# PCB-AC2SLb.net
KiCad netlist of a schematic drawn in EAGLE
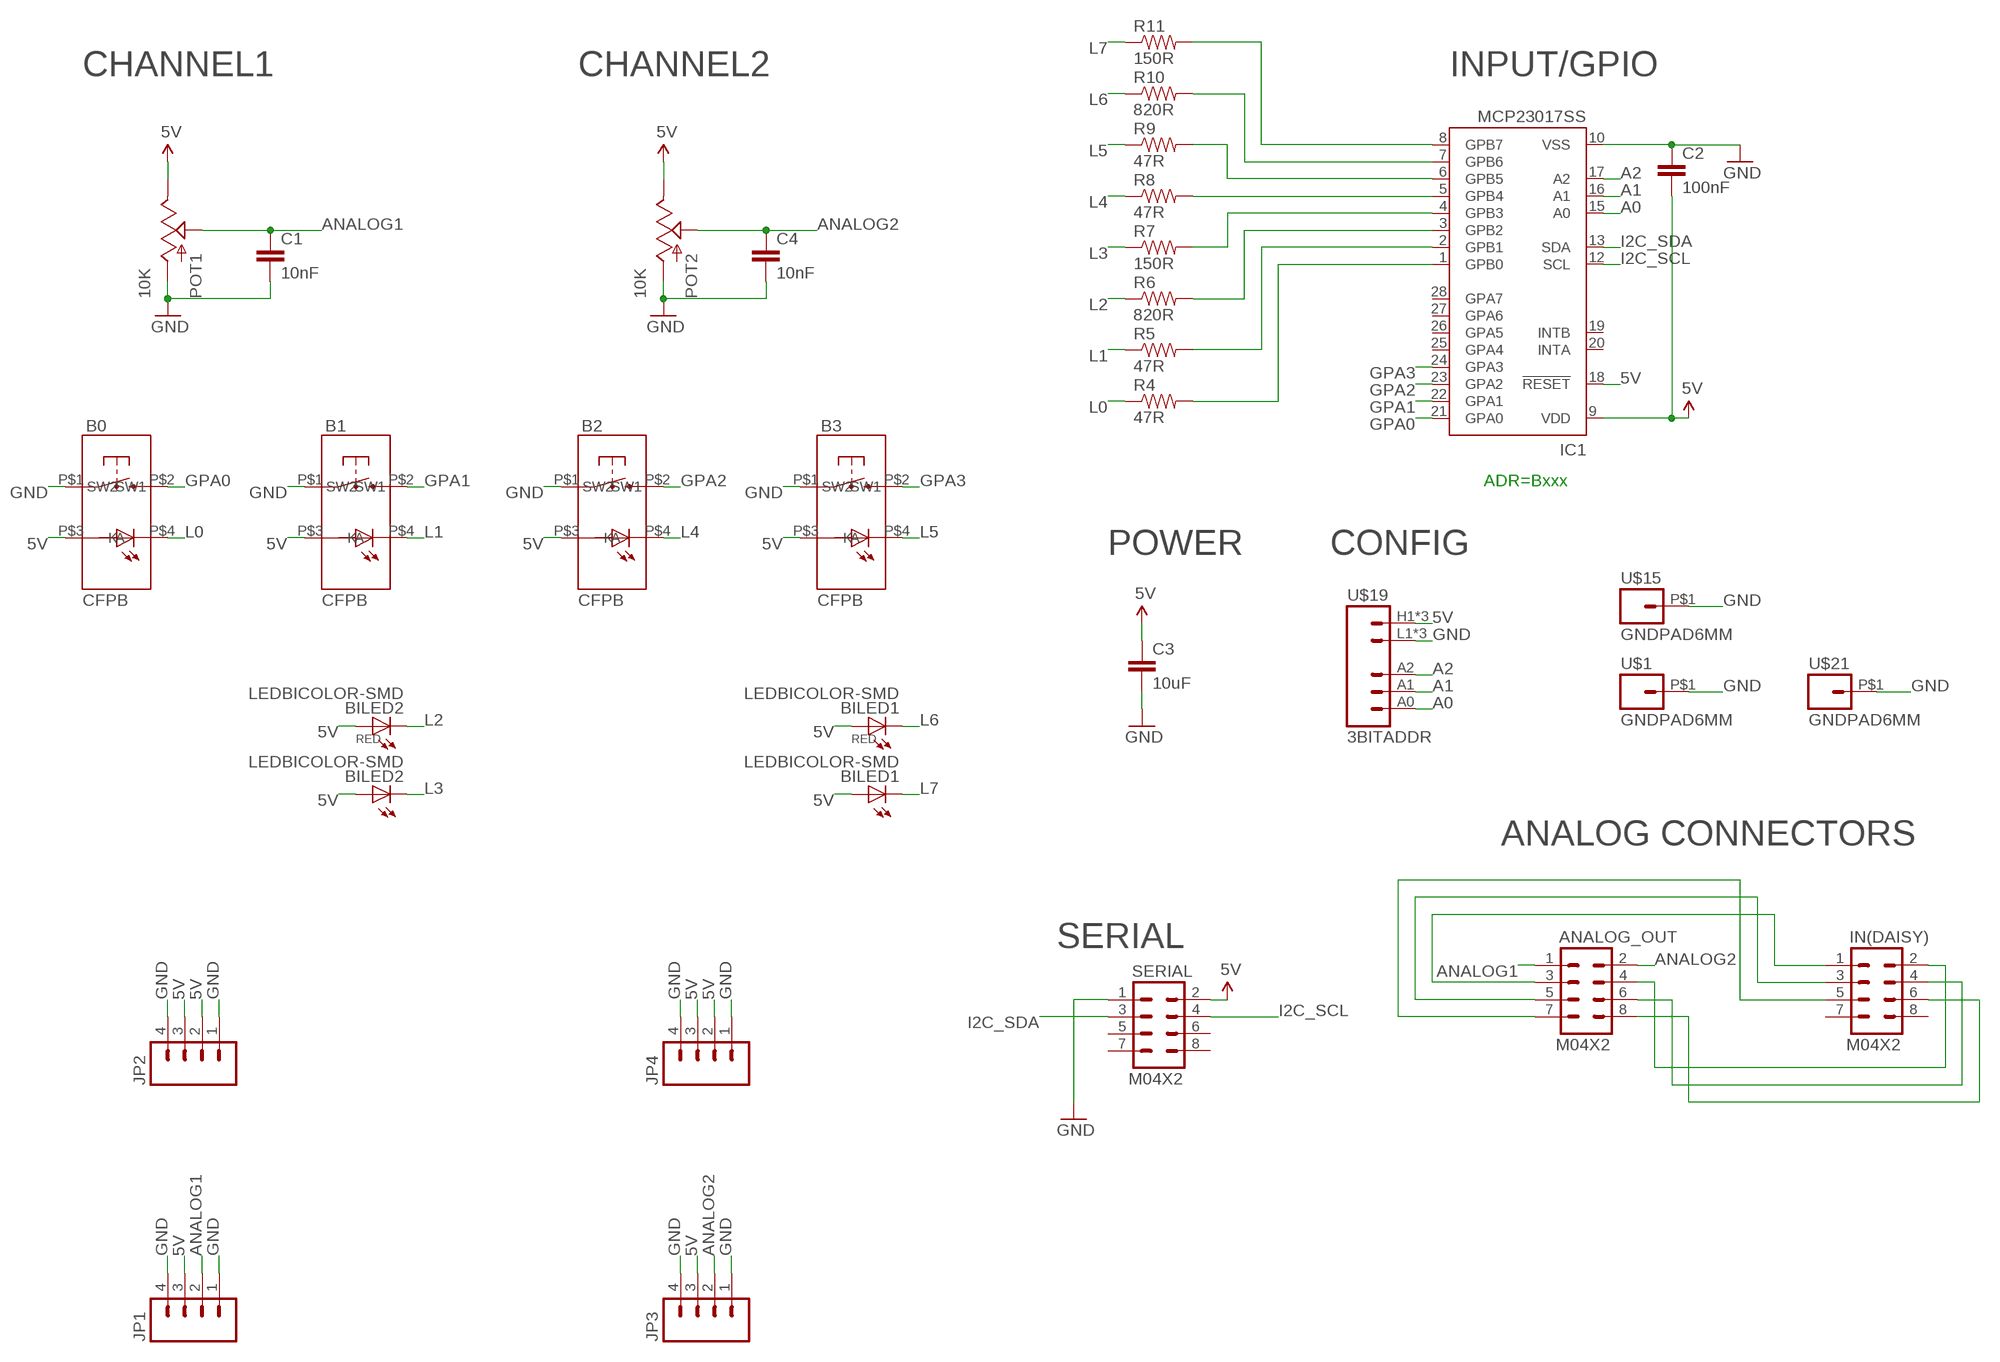
[diagram p0: schematic, sheet 1]

(export (version "E")
  (design (tool "Eeschema 10.0.6"))
  (components
    (comp (ref "ANALOG_OUT")
      (value "M04X2")
      (footprint "eagle-import:2X4")
      (libsource (lib "eagle-import") (part "M04X2"))
    )
    (comp (ref "B0")
      (value "CFPB")
      (footprint "eagle-import:CFPB-6_9MM")
      (libsource (lib "eagle-import") (part "CFPB"))
    )
    (comp (ref "B1")
      (value "CFPB")
      (footprint "eagle-import:CFPB-6_9MM")
      (libsource (lib "eagle-import") (part "CFPB"))
    )
    (comp (ref "B2")
      (value "CFPB")
      (footprint "eagle-import:CFPB-6_9MM")
      (libsource (lib "eagle-import") (part "CFPB"))
    )
    (comp (ref "B3")
      (value "CFPB")
      (footprint "eagle-import:CFPB-6_9MM")
      (libsource (lib "eagle-import") (part "CFPB"))
    )
    (comp (ref "BILED1")
      (value "LEDBICOLOR-SMD")
      (footprint "eagle-import:LEDBICOLOR-SMD")
      (libsource (lib "eagle-import") (part "LEDBICOLOR-SMD"))
    )
    (comp (ref "BILED2")
      (value "LEDBICOLOR-SMD")
      (footprint "eagle-import:LEDBICOLOR-SMD")
      (libsource (lib "eagle-import") (part "LEDBICOLOR-SMD"))
    )
    (comp (ref "C1")
      (value "10nF")
      (footprint "eagle-import:0603-CAP")
      (libsource (lib "eagle-import") (part "CAP0603-CAP"))
    )
    (comp (ref "C2")
      (value "100nF")
      (footprint "eagle-import:0603-CAP")
      (libsource (lib "eagle-import") (part "CAP0603-CAP"))
    )
    (comp (ref "C3")
      (value "10uF")
      (footprint "eagle-import:0805")
      (libsource (lib "eagle-import") (part "CAP0805"))
    )
    (comp (ref "C4")
      (value "10nF")
      (footprint "eagle-import:0603-CAP")
      (libsource (lib "eagle-import") (part "CAP0603-CAP"))
    )
    (comp (ref "IC1")
      (value "MCP23017SS")
      (footprint "eagle-import:SSOP28")
      (fields
        (field (name "MF") "MICROCHIP")
        (field (name "MPN") "MCP23017-E/SS")
        (field (name "MPN_1") "MCP23017-E/SS")
        (field (name "OC_FARNELL") "1467674")
        (field (name "OC_NEWARK") "31K2960")
      )
      (libsource (lib "eagle-import") (part "MCP23017SS"))
    )
    (comp (ref "IN(DAISY)")
      (value "M04X2")
      (footprint "eagle-import:2X4")
      (libsource (lib "eagle-import") (part "M04X2"))
    )
    (comp (ref "JP1")
      (value "M04PTH")
      (footprint "eagle-import:1X04")
      (libsource (lib "eagle-import") (part "M04PTH"))
    )
    (comp (ref "JP2")
      (value "M04PTH")
      (footprint "eagle-import:1X04")
      (libsource (lib "eagle-import") (part "M04PTH"))
    )
    (comp (ref "JP3")
      (value "M04PTH")
      (footprint "eagle-import:1X04")
      (libsource (lib "eagle-import") (part "M04PTH"))
    )
    (comp (ref "JP4")
      (value "M04PTH")
      (footprint "eagle-import:1X04")
      (libsource (lib "eagle-import") (part "M04PTH"))
    )
    (comp (ref "POT1")
      (value "10K")
      (footprint "eagle-import:SLIDER45")
      (libsource (lib "eagle-import") (part "SLIDER45"))
    )
    (comp (ref "POT2")
      (value "10K")
      (footprint "eagle-import:SLIDER45")
      (libsource (lib "eagle-import") (part "SLIDER45"))
    )
    (comp (ref "R4")
      (value "47R")
      (footprint "eagle-import:0603-RES")
      (libsource (lib "eagle-import") (part "RESISTOR0603-RES"))
    )
    (comp (ref "R5")
      (value "47R")
      (footprint "eagle-import:0603-RES")
      (libsource (lib "eagle-import") (part "RESISTOR0603-RES"))
    )
    (comp (ref "R6")
      (value "820R")
      (footprint "eagle-import:0603-RES")
      (libsource (lib "eagle-import") (part "RESISTOR0603-RES"))
    )
    (comp (ref "R7")
      (value "150R")
      (footprint "eagle-import:0603-RES")
      (libsource (lib "eagle-import") (part "RESISTOR0603-RES"))
    )
    (comp (ref "R8")
      (value "47R")
      (footprint "eagle-import:0603-RES")
      (libsource (lib "eagle-import") (part "RESISTOR0603-RES"))
    )
    (comp (ref "R9")
      (value "47R")
      (footprint "eagle-import:0603-RES")
      (libsource (lib "eagle-import") (part "RESISTOR0603-RES"))
    )
    (comp (ref "R10")
      (value "820R")
      (footprint "eagle-import:0603-RES")
      (libsource (lib "eagle-import") (part "RESISTOR0603-RES"))
    )
    (comp (ref "R11")
      (value "150R")
      (footprint "eagle-import:0603-RES")
      (libsource (lib "eagle-import") (part "RESISTOR0603-RES"))
    )
    (comp (ref "SERIAL")
      (value "M04X2")
      (footprint "eagle-import:2X4")
      (libsource (lib "eagle-import") (part "M04X2"))
    )
    (comp (ref "U$1")
      (value "GNDPAD6MM")
      (footprint "eagle-import:3.2MMPAD6MM")
      (libsource (lib "eagle-import") (part "GNDPAD6MM"))
    )
    (comp (ref "U$15")
      (value "GNDPAD6MM")
      (footprint "eagle-import:3.2MMPAD6MM")
      (libsource (lib "eagle-import") (part "GNDPAD6MM"))
    )
    (comp (ref "U$19")
      (value "3BITADDR")
      (footprint "eagle-import:3BITADDR")
      (libsource (lib "eagle-import") (part "3BITADDR"))
    )
    (comp (ref "U$21")
      (value "GNDPAD6MM")
      (footprint "eagle-import:3.2MMPAD6MM")
      (libsource (lib "eagle-import") (part "GNDPAD6MM"))
    )
  )
  (nets
    (net (code "1") (name "5V") (class "Default")
      (node (ref "B0") (pin "P$3") (pinfunction "A_P$3") (pintype "bidirectional"))
      (node (ref "B1") (pin "P$3") (pinfunction "A_P$3") (pintype "bidirectional"))
      (node (ref "B2") (pin "P$3") (pinfunction "A_P$3") (pintype "bidirectional"))
      (node (ref "B3") (pin "P$3") (pinfunction "A_P$3") (pintype "bidirectional"))
      (node (ref "BILED1") (pin "P$1") (pinfunction "A_P$1") (pintype "passive"))
      (node (ref "BILED1") (pin "P$3") (pinfunction "A1_P$3") (pintype "passive"))
      (node (ref "BILED2") (pin "P$1") (pinfunction "A_P$1") (pintype "passive"))
      (node (ref "BILED2") (pin "P$3") (pinfunction "A1_P$3") (pintype "passive"))
      (node (ref "C2") (pin "2") (pinfunction "2_2") (pintype "passive"))
      (node (ref "C3") (pin "1") (pinfunction "1_1") (pintype "passive"))
      (node (ref "IC1") (pin "18") (pinfunction "~{RESET}_18") (pintype "input"))
      (node (ref "IC1") (pin "9") (pinfunction "VDD_9") (pintype "power_in"))
      (node (ref "JP1") (pin "3") (pinfunction "3_3") (pintype "passive"))
      (node (ref "JP2") (pin "2") (pinfunction "2_2") (pintype "passive"))
      (node (ref "JP2") (pin "3") (pinfunction "3_3") (pintype "passive"))
      (node (ref "JP3") (pin "3") (pinfunction "3_3") (pintype "passive"))
      (node (ref "JP4") (pin "2") (pinfunction "2_2") (pintype "passive"))
      (node (ref "JP4") (pin "3") (pinfunction "3_3") (pintype "passive"))
      (node (ref "POT1") (pin "1") (pinfunction "E_1") (pintype "passive"))
      (node (ref "POT2") (pin "1") (pinfunction "E_1") (pintype "passive"))
      (node (ref "SERIAL") (pin "2") (pinfunction "2_2") (pintype "passive"))
      (node (ref "U$19") (pin "H1") (pinfunction "VCC_H1") (pintype "passive"))
      (node (ref "U$19") (pin "H2") (pinfunction "VCC_H2") (pintype "passive"))
      (node (ref "U$19") (pin "H3") (pinfunction "VCC_H3") (pintype "passive"))
    )
    (net (code "2") (name "A0") (class "Default")
      (node (ref "IC1") (pin "15") (pinfunction "A0_15") (pintype "input"))
      (node (ref "U$19") (pin "A0") (pinfunction "A0_A0") (pintype "passive"))
    )
    (net (code "3") (name "A1") (class "Default")
      (node (ref "IC1") (pin "16") (pinfunction "A1_16") (pintype "input"))
      (node (ref "U$19") (pin "A1") (pinfunction "A1_A1") (pintype "passive"))
    )
    (net (code "4") (name "A2") (class "Default")
      (node (ref "IC1") (pin "17") (pinfunction "A2_17") (pintype "input"))
      (node (ref "U$19") (pin "A2") (pinfunction "A2_A2") (pintype "passive"))
    )
    (net (code "5") (name "ANALOG1") (class "Default")
      (node (ref "ANALOG_OUT") (pin "1") (pinfunction "1_1") (pintype "passive"))
      (node (ref "C1") (pin "1") (pinfunction "1_1") (pintype "passive"))
      (node (ref "JP1") (pin "2") (pinfunction "2_2") (pintype "passive"))
      (node (ref "POT1") (pin "2A") (pinfunction "S_2A") (pintype "passive"))
    )
    (net (code "6") (name "ANALOG2") (class "Default")
      (node (ref "ANALOG_OUT") (pin "2") (pinfunction "2_2") (pintype "passive"))
      (node (ref "C4") (pin "1") (pinfunction "1_1") (pintype "passive"))
      (node (ref "JP3") (pin "2") (pinfunction "2_2") (pintype "passive"))
      (node (ref "POT2") (pin "2A") (pinfunction "S_2A") (pintype "passive"))
    )
    (net (code "7") (name "GND") (class "Default")
      (node (ref "B0") (pin "P$1") (pinfunction "SW1_P$1") (pintype "bidirectional"))
      (node (ref "B1") (pin "P$1") (pinfunction "SW1_P$1") (pintype "bidirectional"))
      (node (ref "B2") (pin "P$1") (pinfunction "SW1_P$1") (pintype "bidirectional"))
      (node (ref "B3") (pin "P$1") (pinfunction "SW1_P$1") (pintype "bidirectional"))
      (node (ref "C1") (pin "2") (pinfunction "2_2") (pintype "passive"))
      (node (ref "C2") (pin "1") (pinfunction "1_1") (pintype "passive"))
      (node (ref "C3") (pin "2") (pinfunction "2_2") (pintype "passive"))
      (node (ref "C4") (pin "2") (pinfunction "2_2") (pintype "passive"))
      (node (ref "IC1") (pin "10") (pinfunction "VSS_10") (pintype "power_in"))
      (node (ref "JP1") (pin "1") (pinfunction "1_1") (pintype "passive"))
      (node (ref "JP1") (pin "4") (pinfunction "4_4") (pintype "passive"))
      (node (ref "JP2") (pin "1") (pinfunction "1_1") (pintype "passive"))
      (node (ref "JP2") (pin "4") (pinfunction "4_4") (pintype "passive"))
      (node (ref "JP3") (pin "1") (pinfunction "1_1") (pintype "passive"))
      (node (ref "JP3") (pin "4") (pinfunction "4_4") (pintype "passive"))
      (node (ref "JP4") (pin "1") (pinfunction "1_1") (pintype "passive"))
      (node (ref "JP4") (pin "4") (pinfunction "4_4") (pintype "passive"))
      (node (ref "POT1") (pin "3") (pinfunction "A_3") (pintype "passive"))
      (node (ref "POT2") (pin "3") (pinfunction "A_3") (pintype "passive"))
      (node (ref "SERIAL") (pin "1") (pinfunction "1_1") (pintype "passive"))
      (node (ref "U$1") (pin "P$1") (pinfunction "1_P$1") (pintype "passive"))
      (node (ref "U$15") (pin "P$1") (pinfunction "1_P$1") (pintype "passive"))
      (node (ref "U$19") (pin "L1") (pinfunction "GND_L1") (pintype "passive"))
      (node (ref "U$19") (pin "L2") (pinfunction "GND_L2") (pintype "passive"))
      (node (ref "U$19") (pin "L3") (pinfunction "GND_L3") (pintype "passive"))
      (node (ref "U$21") (pin "P$1") (pinfunction "1_P$1") (pintype "passive"))
    )
    (net (code "8") (name "GPA0") (class "Default")
      (node (ref "B0") (pin "P$2") (pinfunction "SW2_P$2") (pintype "bidirectional"))
      (node (ref "IC1") (pin "21") (pinfunction "GPA0_21") (pintype "bidirectional"))
    )
    (net (code "9") (name "GPA1") (class "Default")
      (node (ref "B1") (pin "P$2") (pinfunction "SW2_P$2") (pintype "bidirectional"))
      (node (ref "IC1") (pin "22") (pinfunction "GPA1_22") (pintype "bidirectional"))
    )
    (net (code "10") (name "GPA2") (class "Default")
      (node (ref "B2") (pin "P$2") (pinfunction "SW2_P$2") (pintype "bidirectional"))
      (node (ref "IC1") (pin "23") (pinfunction "GPA2_23") (pintype "bidirectional"))
    )
    (net (code "11") (name "GPA3") (class "Default")
      (node (ref "B3") (pin "P$2") (pinfunction "SW2_P$2") (pintype "bidirectional"))
      (node (ref "IC1") (pin "24") (pinfunction "GPA3_24") (pintype "bidirectional"))
    )
    (net (code "12") (name "I2C_SCL") (class "Default")
      (node (ref "IC1") (pin "12") (pinfunction "SCL_12") (pintype "input"))
      (node (ref "SERIAL") (pin "4") (pinfunction "4_4") (pintype "passive"))
    )
    (net (code "13") (name "I2C_SDA") (class "Default")
      (node (ref "IC1") (pin "13") (pinfunction "SDA_13") (pintype "bidirectional"))
      (node (ref "SERIAL") (pin "3") (pinfunction "3_3") (pintype "passive"))
    )
    (net (code "14") (name "L0") (class "Default")
      (node (ref "B0") (pin "P$4") (pinfunction "K_P$4") (pintype "bidirectional"))
      (node (ref "R4") (pin "1") (pinfunction "1_1") (pintype "passive"))
    )
    (net (code "15") (name "L1") (class "Default")
      (node (ref "B1") (pin "P$4") (pinfunction "K_P$4") (pintype "bidirectional"))
      (node (ref "R5") (pin "1") (pinfunction "1_1") (pintype "passive"))
    )
    (net (code "16") (name "L2") (class "Default")
      (node (ref "BILED2") (pin "P$2") (pinfunction "C_P$2") (pintype "passive"))
      (node (ref "R6") (pin "1") (pinfunction "1_1") (pintype "passive"))
    )
    (net (code "17") (name "L3") (class "Default")
      (node (ref "BILED2") (pin "P$4") (pinfunction "C1_P$4") (pintype "passive"))
      (node (ref "R7") (pin "1") (pinfunction "1_1") (pintype "passive"))
    )
    (net (code "18") (name "L4") (class "Default")
      (node (ref "B2") (pin "P$4") (pinfunction "K_P$4") (pintype "bidirectional"))
      (node (ref "R8") (pin "1") (pinfunction "1_1") (pintype "passive"))
    )
    (net (code "19") (name "L5") (class "Default")
      (node (ref "B3") (pin "P$4") (pinfunction "K_P$4") (pintype "bidirectional"))
      (node (ref "R9") (pin "1") (pinfunction "1_1") (pintype "passive"))
    )
    (net (code "20") (name "L6") (class "Default")
      (node (ref "BILED1") (pin "P$2") (pinfunction "C_P$2") (pintype "passive"))
      (node (ref "R10") (pin "1") (pinfunction "1_1") (pintype "passive"))
    )
    (net (code "21") (name "L7") (class "Default")
      (node (ref "BILED1") (pin "P$4") (pinfunction "C1_P$4") (pintype "passive"))
      (node (ref "R11") (pin "1") (pinfunction "1_1") (pintype "passive"))
    )
    (net (code "22") (name "Net-(ANALOG_OUT-Pad3)") (class "Default")
      (node (ref "ANALOG_OUT") (pin "3") (pinfunction "3_3") (pintype "passive"))
      (node (ref "IN(DAISY)") (pin "1") (pinfunction "1_1") (pintype "passive"))
    )
    (net (code "23") (name "Net-(ANALOG_OUT-Pad4)") (class "Default")
      (node (ref "ANALOG_OUT") (pin "4") (pinfunction "4_4") (pintype "passive"))
      (node (ref "IN(DAISY)") (pin "2") (pinfunction "2_2") (pintype "passive"))
    )
    (net (code "24") (name "Net-(ANALOG_OUT-Pad5)") (class "Default")
      (node (ref "ANALOG_OUT") (pin "5") (pinfunction "5_5") (pintype "passive"))
      (node (ref "IN(DAISY)") (pin "3") (pinfunction "3_3") (pintype "passive"))
    )
    (net (code "25") (name "Net-(ANALOG_OUT-Pad6)") (class "Default")
      (node (ref "ANALOG_OUT") (pin "6") (pinfunction "6_6") (pintype "passive"))
      (node (ref "IN(DAISY)") (pin "4") (pinfunction "4_4") (pintype "passive"))
    )
    (net (code "26") (name "Net-(ANALOG_OUT-Pad7)") (class "Default")
      (node (ref "ANALOG_OUT") (pin "7") (pinfunction "7_7") (pintype "passive"))
      (node (ref "IN(DAISY)") (pin "5") (pinfunction "5_5") (pintype "passive"))
    )
    (net (code "27") (name "Net-(ANALOG_OUT-Pad8)") (class "Default")
      (node (ref "ANALOG_OUT") (pin "8") (pinfunction "8_8") (pintype "passive"))
      (node (ref "IN(DAISY)") (pin "6") (pinfunction "6_6") (pintype "passive"))
    )
    (net (code "28") (name "Net-(IC1-GPB0)") (class "Default")
      (node (ref "IC1") (pin "1") (pinfunction "GPB0_1") (pintype "bidirectional"))
      (node (ref "R4") (pin "2") (pinfunction "2_2") (pintype "passive"))
    )
    (net (code "29") (name "Net-(IC1-GPB1)") (class "Default")
      (node (ref "IC1") (pin "2") (pinfunction "GPB1_2") (pintype "bidirectional"))
      (node (ref "R5") (pin "2") (pinfunction "2_2") (pintype "passive"))
    )
    (net (code "30") (name "Net-(IC1-GPB2)") (class "Default")
      (node (ref "IC1") (pin "3") (pinfunction "GPB2_3") (pintype "bidirectional"))
      (node (ref "R6") (pin "2") (pinfunction "2_2") (pintype "passive"))
    )
    (net (code "31") (name "Net-(IC1-GPB3)") (class "Default")
      (node (ref "IC1") (pin "4") (pinfunction "GPB3_4") (pintype "bidirectional"))
      (node (ref "R7") (pin "2") (pinfunction "2_2") (pintype "passive"))
    )
    (net (code "32") (name "Net-(IC1-GPB4)") (class "Default")
      (node (ref "IC1") (pin "5") (pinfunction "GPB4_5") (pintype "bidirectional"))
      (node (ref "R8") (pin "2") (pinfunction "2_2") (pintype "passive"))
    )
    (net (code "33") (name "Net-(IC1-GPB5)") (class "Default")
      (node (ref "IC1") (pin "6") (pinfunction "GPB5_6") (pintype "bidirectional"))
      (node (ref "R9") (pin "2") (pinfunction "2_2") (pintype "passive"))
    )
    (net (code "34") (name "Net-(IC1-GPB6)") (class "Default")
      (node (ref "IC1") (pin "7") (pinfunction "GPB6_7") (pintype "bidirectional"))
      (node (ref "R10") (pin "2") (pinfunction "2_2") (pintype "passive"))
    )
    (net (code "35") (name "Net-(IC1-GPB7)") (class "Default")
      (node (ref "IC1") (pin "8") (pinfunction "GPB7_8") (pintype "bidirectional"))
      (node (ref "R11") (pin "2") (pinfunction "2_2") (pintype "passive"))
    )
    (net (code "36") (name "unconnected-(IC1-GPA4-Pad25)") (class "Default")
      (node (ref "IC1") (pin "25") (pinfunction "GPA4_25") (pintype "bidirectional"))
    )
    (net (code "37") (name "unconnected-(IC1-GPA5-Pad26)") (class "Default")
      (node (ref "IC1") (pin "26") (pinfunction "GPA5_26") (pintype "bidirectional"))
    )
    (net (code "38") (name "unconnected-(IC1-GPA6-Pad27)") (class "Default")
      (node (ref "IC1") (pin "27") (pinfunction "GPA6_27") (pintype "bidirectional"))
    )
    (net (code "39") (name "unconnected-(IC1-GPA7-Pad28)") (class "Default")
      (node (ref "IC1") (pin "28") (pinfunction "GPA7_28") (pintype "bidirectional"))
    )
    (net (code "40") (name "unconnected-(IC1-INTA-Pad20)") (class "Default")
      (node (ref "IC1") (pin "20") (pinfunction "INTA_20") (pintype "output"))
    )
    (net (code "41") (name "unconnected-(IC1-INTB-Pad19)") (class "Default")
      (node (ref "IC1") (pin "19") (pinfunction "INTB_19") (pintype "output"))
    )
    (net (code "42") (name "unconnected-(IN(DAISY)-Pad7)") (class "Default")
      (node (ref "IN(DAISY)") (pin "7") (pinfunction "7_7") (pintype "passive"))
    )
    (net (code "43") (name "unconnected-(IN(DAISY)-Pad8)") (class "Default")
      (node (ref "IN(DAISY)") (pin "8") (pinfunction "8_8") (pintype "passive"))
    )
    (net (code "44") (name "unconnected-(SERIAL-Pad5)") (class "Default")
      (node (ref "SERIAL") (pin "5") (pinfunction "5_5") (pintype "passive"))
    )
    (net (code "45") (name "unconnected-(SERIAL-Pad6)") (class "Default")
      (node (ref "SERIAL") (pin "6") (pinfunction "6_6") (pintype "passive"))
    )
    (net (code "46") (name "unconnected-(SERIAL-Pad7)") (class "Default")
      (node (ref "SERIAL") (pin "7") (pinfunction "7_7") (pintype "passive"))
    )
    (net (code "47") (name "unconnected-(SERIAL-Pad8)") (class "Default")
      (node (ref "SERIAL") (pin "8") (pinfunction "8_8") (pintype "passive"))
    )
  )
)
